# RC_Engine_Sound_ESP32.net
KiCad netlist of a schematic drawn in EAGLE
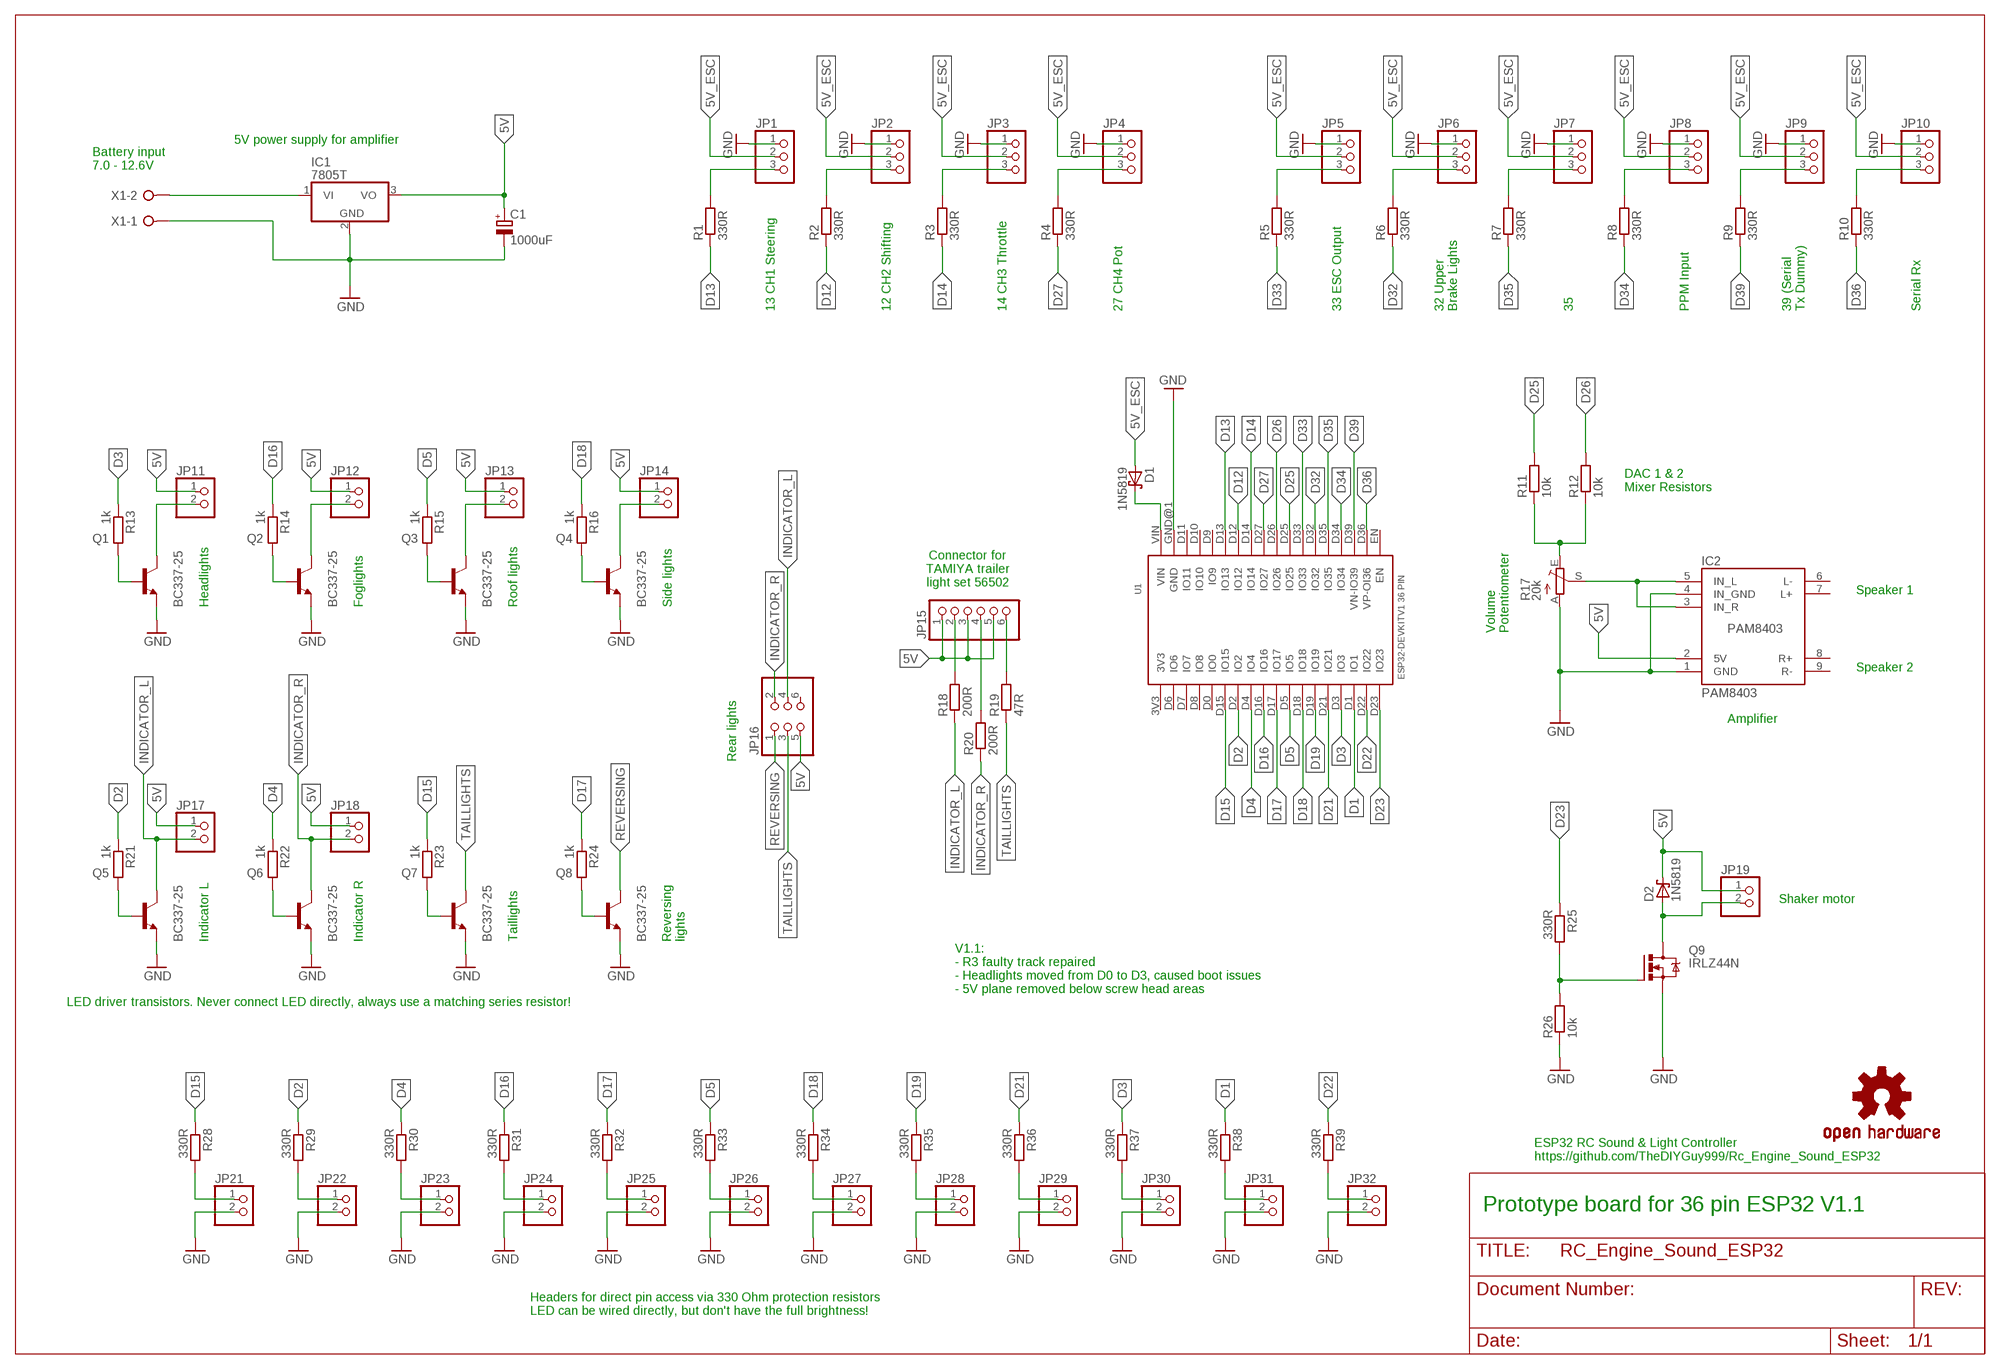
[diagram p0: schematic, sheet 1]

(export (version "E")
  (design (tool "Eeschema 10.0.6"))
  (components
    (comp (ref "C1")
      (value "1000uF")
      (footprint "eagle-import:E5-10,5")
      (libsource (lib "eagle-import") (part "CPOL-EUE5-10.5"))
    )
    (comp (ref "D1")
      (value "1N5819")
      (footprint "eagle-import:DO35-7")
      (libsource (lib "eagle-import") (part "SCHOTTKY-DIODEDO35-7"))
    )
    (comp (ref "D2")
      (value "1N5819")
      (footprint "eagle-import:DO35-7")
      (libsource (lib "eagle-import") (part "SCHOTTKY-DIODEDO35-7"))
    )
    (comp (ref "IC1")
      (value "7805T")
      (footprint "eagle-import:TO220H")
      (libsource (lib "eagle-import") (part "78T05"))
    )
    (comp (ref "IC2")
      (value "PAM8403")
      (footprint "eagle-import:PAM8403")
      (libsource (lib "eagle-import") (part "PAM8403"))
    )
    (comp (ref "JP1")
      (value "PINHD-1X3")
      (footprint "eagle-import:1X03")
      (libsource (lib "eagle-import") (part "PINHD-1X3"))
    )
    (comp (ref "JP2")
      (value "PINHD-1X3")
      (footprint "eagle-import:1X03")
      (libsource (lib "eagle-import") (part "PINHD-1X3"))
    )
    (comp (ref "JP3")
      (value "PINHD-1X3")
      (footprint "eagle-import:1X03")
      (libsource (lib "eagle-import") (part "PINHD-1X3"))
    )
    (comp (ref "JP4")
      (value "PINHD-1X3")
      (footprint "eagle-import:1X03")
      (libsource (lib "eagle-import") (part "PINHD-1X3"))
    )
    (comp (ref "JP5")
      (value "PINHD-1X3")
      (footprint "eagle-import:1X03")
      (libsource (lib "eagle-import") (part "PINHD-1X3"))
    )
    (comp (ref "JP6")
      (value "PINHD-1X3")
      (footprint "eagle-import:1X03")
      (libsource (lib "eagle-import") (part "PINHD-1X3"))
    )
    (comp (ref "JP7")
      (value "PINHD-1X3")
      (footprint "eagle-import:1X03")
      (libsource (lib "eagle-import") (part "PINHD-1X3"))
    )
    (comp (ref "JP8")
      (value "PINHD-1X3")
      (footprint "eagle-import:1X03")
      (libsource (lib "eagle-import") (part "PINHD-1X3"))
    )
    (comp (ref "JP9")
      (value "PINHD-1X3")
      (footprint "eagle-import:1X03")
      (libsource (lib "eagle-import") (part "PINHD-1X3"))
    )
    (comp (ref "JP10")
      (value "PINHD-1X3")
      (footprint "eagle-import:1X03")
      (libsource (lib "eagle-import") (part "PINHD-1X3"))
    )
    (comp (ref "JP11")
      (value "PINHD-1X2")
      (footprint "eagle-import:1X02")
      (libsource (lib "eagle-import") (part "PINHD-1X2"))
    )
    (comp (ref "JP12")
      (value "PINHD-1X2")
      (footprint "eagle-import:1X02")
      (libsource (lib "eagle-import") (part "PINHD-1X2"))
    )
    (comp (ref "JP13")
      (value "PINHD-1X2")
      (footprint "eagle-import:1X02")
      (libsource (lib "eagle-import") (part "PINHD-1X2"))
    )
    (comp (ref "JP14")
      (value "PINHD-1X2")
      (footprint "eagle-import:1X02")
      (libsource (lib "eagle-import") (part "PINHD-1X2"))
    )
    (comp (ref "JP15")
      (value "PINHD-1X6")
      (footprint "eagle-import:1X06")
      (libsource (lib "eagle-import") (part "PINHD-1X6"))
    )
    (comp (ref "JP16")
      (value "PINHD-2X3")
      (footprint "eagle-import:2X03")
      (libsource (lib "eagle-import") (part "PINHD-2X3"))
    )
    (comp (ref "JP17")
      (value "PINHD-1X2")
      (footprint "eagle-import:1X02")
      (libsource (lib "eagle-import") (part "PINHD-1X2"))
    )
    (comp (ref "JP18")
      (value "PINHD-1X2")
      (footprint "eagle-import:1X02")
      (libsource (lib "eagle-import") (part "PINHD-1X2"))
    )
    (comp (ref "JP19")
      (value "PINHD-1X2")
      (footprint "eagle-import:1X02")
      (libsource (lib "eagle-import") (part "PINHD-1X2"))
    )
    (comp (ref "JP21")
      (value "PINHD-1X2")
      (footprint "eagle-import:1X02")
      (libsource (lib "eagle-import") (part "PINHD-1X2"))
    )
    (comp (ref "JP22")
      (value "PINHD-1X2")
      (footprint "eagle-import:1X02")
      (libsource (lib "eagle-import") (part "PINHD-1X2"))
    )
    (comp (ref "JP23")
      (value "PINHD-1X2")
      (footprint "eagle-import:1X02")
      (libsource (lib "eagle-import") (part "PINHD-1X2"))
    )
    (comp (ref "JP24")
      (value "PINHD-1X2")
      (footprint "eagle-import:1X02")
      (libsource (lib "eagle-import") (part "PINHD-1X2"))
    )
    (comp (ref "JP25")
      (value "PINHD-1X2")
      (footprint "eagle-import:1X02")
      (libsource (lib "eagle-import") (part "PINHD-1X2"))
    )
    (comp (ref "JP26")
      (value "PINHD-1X2")
      (footprint "eagle-import:1X02")
      (libsource (lib "eagle-import") (part "PINHD-1X2"))
    )
    (comp (ref "JP27")
      (value "PINHD-1X2")
      (footprint "eagle-import:1X02")
      (libsource (lib "eagle-import") (part "PINHD-1X2"))
    )
    (comp (ref "JP28")
      (value "PINHD-1X2")
      (footprint "eagle-import:1X02")
      (libsource (lib "eagle-import") (part "PINHD-1X2"))
    )
    (comp (ref "JP29")
      (value "PINHD-1X2")
      (footprint "eagle-import:1X02")
      (libsource (lib "eagle-import") (part "PINHD-1X2"))
    )
    (comp (ref "JP30")
      (value "PINHD-1X2")
      (footprint "eagle-import:1X02")
      (libsource (lib "eagle-import") (part "PINHD-1X2"))
    )
    (comp (ref "JP31")
      (value "PINHD-1X2")
      (footprint "eagle-import:1X02")
      (libsource (lib "eagle-import") (part "PINHD-1X2"))
    )
    (comp (ref "JP32")
      (value "PINHD-1X2")
      (footprint "eagle-import:1X02")
      (libsource (lib "eagle-import") (part "PINHD-1X2"))
    )
    (comp (ref "LOGO1")
      (value "OSHW-LOGOM")
      (footprint "eagle-import:OSHW-LOGO-M")
      (libsource (lib "eagle-import") (part "OSHW-LOGOM"))
    )
    (comp (ref "Q1")
      (value "BC337-25")
      (footprint "eagle-import:TO92")
      (libsource (lib "eagle-import") (part "BC337-25"))
    )
    (comp (ref "Q2")
      (value "BC337-25")
      (footprint "eagle-import:TO92")
      (libsource (lib "eagle-import") (part "BC337-25"))
    )
    (comp (ref "Q3")
      (value "BC337-25")
      (footprint "eagle-import:TO92")
      (libsource (lib "eagle-import") (part "BC337-25"))
    )
    (comp (ref "Q4")
      (value "BC337-25")
      (footprint "eagle-import:TO92")
      (libsource (lib "eagle-import") (part "BC337-25"))
    )
    (comp (ref "Q5")
      (value "BC337-25")
      (footprint "eagle-import:TO92")
      (libsource (lib "eagle-import") (part "BC337-25"))
    )
    (comp (ref "Q6")
      (value "BC337-25")
      (footprint "eagle-import:TO92")
      (libsource (lib "eagle-import") (part "BC337-25"))
    )
    (comp (ref "Q7")
      (value "BC337-25")
      (footprint "eagle-import:TO92")
      (libsource (lib "eagle-import") (part "BC337-25"))
    )
    (comp (ref "Q8")
      (value "BC337-25")
      (footprint "eagle-import:TO92")
      (libsource (lib "eagle-import") (part "BC337-25"))
    )
    (comp (ref "Q9")
      (value "IRLZ44N")
      (footprint "eagle-import:TO220BV")
      (libsource (lib "eagle-import") (part "IRF540"))
    )
    (comp (ref "R1")
      (value "330R")
      (footprint "eagle-import:0207_2V")
      (libsource (lib "eagle-import") (part "R-EU_0207/2V"))
    )
    (comp (ref "R2")
      (value "330R")
      (footprint "eagle-import:0207_2V")
      (libsource (lib "eagle-import") (part "R-EU_0207/2V"))
    )
    (comp (ref "R3")
      (value "330R")
      (footprint "eagle-import:0207_2V")
      (libsource (lib "eagle-import") (part "R-EU_0207/2V"))
    )
    (comp (ref "R4")
      (value "330R")
      (footprint "eagle-import:0207_2V")
      (libsource (lib "eagle-import") (part "R-EU_0207/2V"))
    )
    (comp (ref "R5")
      (value "330R")
      (footprint "eagle-import:0207_2V")
      (libsource (lib "eagle-import") (part "R-EU_0207/2V"))
    )
    (comp (ref "R6")
      (value "330R")
      (footprint "eagle-import:0207_2V")
      (libsource (lib "eagle-import") (part "R-EU_0207/2V"))
    )
    (comp (ref "R7")
      (value "330R")
      (footprint "eagle-import:0207_2V")
      (libsource (lib "eagle-import") (part "R-EU_0207/2V"))
    )
    (comp (ref "R8")
      (value "330R")
      (footprint "eagle-import:0207_2V")
      (libsource (lib "eagle-import") (part "R-EU_0207/2V"))
    )
    (comp (ref "R9")
      (value "330R")
      (footprint "eagle-import:0207_2V")
      (libsource (lib "eagle-import") (part "R-EU_0207/2V"))
    )
    (comp (ref "R10")
      (value "330R")
      (footprint "eagle-import:0207_2V")
      (libsource (lib "eagle-import") (part "R-EU_0207/2V"))
    )
    (comp (ref "R11")
      (value "10k")
      (footprint "eagle-import:0207_10")
      (libsource (lib "eagle-import") (part "R-EU_0207/10"))
    )
    (comp (ref "R12")
      (value "10k")
      (footprint "eagle-import:0207_10")
      (libsource (lib "eagle-import") (part "R-EU_0207/10"))
    )
    (comp (ref "R13")
      (value "1k")
      (footprint "eagle-import:0207_2V")
      (libsource (lib "eagle-import") (part "R-EU_0207/2V"))
    )
    (comp (ref "R14")
      (value "1k")
      (footprint "eagle-import:0207_2V")
      (libsource (lib "eagle-import") (part "R-EU_0207/2V"))
    )
    (comp (ref "R15")
      (value "1k")
      (footprint "eagle-import:0207_2V")
      (libsource (lib "eagle-import") (part "R-EU_0207/2V"))
    )
    (comp (ref "R16")
      (value "1k")
      (footprint "eagle-import:0207_2V")
      (libsource (lib "eagle-import") (part "R-EU_0207/2V"))
    )
    (comp (ref "R17")
      (value "20k")
      (footprint "eagle-import:S64W")
      (libsource (lib "eagle-import") (part "TRIM_EU-S64W"))
    )
    (comp (ref "R18")
      (value "200R")
      (footprint "eagle-import:0207_2V")
      (libsource (lib "eagle-import") (part "R-EU_0207/2V"))
    )
    (comp (ref "R19")
      (value "47R")
      (footprint "eagle-import:0207_2V")
      (libsource (lib "eagle-import") (part "R-EU_0207/2V"))
    )
    (comp (ref "R20")
      (value "200R")
      (footprint "eagle-import:0207_2V")
      (libsource (lib "eagle-import") (part "R-EU_0207/2V"))
    )
    (comp (ref "R21")
      (value "1k")
      (footprint "eagle-import:0207_2V")
      (libsource (lib "eagle-import") (part "R-EU_0207/2V"))
    )
    (comp (ref "R22")
      (value "1k")
      (footprint "eagle-import:0207_2V")
      (libsource (lib "eagle-import") (part "R-EU_0207/2V"))
    )
    (comp (ref "R23")
      (value "1k")
      (footprint "eagle-import:0207_2V")
      (libsource (lib "eagle-import") (part "R-EU_0207/2V"))
    )
    (comp (ref "R24")
      (value "1k")
      (footprint "eagle-import:0207_2V")
      (libsource (lib "eagle-import") (part "R-EU_0207/2V"))
    )
    (comp (ref "R25")
      (value "330R")
      (footprint "eagle-import:0207_2V")
      (libsource (lib "eagle-import") (part "R-EU_0207/2V"))
    )
    (comp (ref "R26")
      (value "10k")
      (footprint "eagle-import:0207_2V")
      (libsource (lib "eagle-import") (part "R-EU_0207/2V"))
    )
    (comp (ref "R28")
      (value "330R")
      (footprint "eagle-import:0207_2V")
      (libsource (lib "eagle-import") (part "R-EU_0207/2V"))
    )
    (comp (ref "R29")
      (value "330R")
      (footprint "eagle-import:0207_2V")
      (libsource (lib "eagle-import") (part "R-EU_0207/2V"))
    )
    (comp (ref "R30")
      (value "330R")
      (footprint "eagle-import:0207_2V")
      (libsource (lib "eagle-import") (part "R-EU_0207/2V"))
    )
    (comp (ref "R31")
      (value "330R")
      (footprint "eagle-import:0207_2V")
      (libsource (lib "eagle-import") (part "R-EU_0207/2V"))
    )
    (comp (ref "R32")
      (value "330R")
      (footprint "eagle-import:0207_2V")
      (libsource (lib "eagle-import") (part "R-EU_0207/2V"))
    )
    (comp (ref "R33")
      (value "330R")
      (footprint "eagle-import:0207_2V")
      (libsource (lib "eagle-import") (part "R-EU_0207/2V"))
    )
    (comp (ref "R34")
      (value "330R")
      (footprint "eagle-import:0207_2V")
      (libsource (lib "eagle-import") (part "R-EU_0207/2V"))
    )
    (comp (ref "R35")
      (value "330R")
      (footprint "eagle-import:0207_2V")
      (libsource (lib "eagle-import") (part "R-EU_0207/2V"))
    )
    (comp (ref "R36")
      (value "330R")
      (footprint "eagle-import:0207_2V")
      (libsource (lib "eagle-import") (part "R-EU_0207/2V"))
    )
    (comp (ref "R37")
      (value "330R")
      (footprint "eagle-import:0207_2V")
      (libsource (lib "eagle-import") (part "R-EU_0207/2V"))
    )
    (comp (ref "R38")
      (value "330R")
      (footprint "eagle-import:0207_2V")
      (libsource (lib "eagle-import") (part "R-EU_0207/2V"))
    )
    (comp (ref "R39")
      (value "330R")
      (footprint "eagle-import:0207_2V")
      (libsource (lib "eagle-import") (part "R-EU_0207/2V"))
    )
    (comp (ref "U1")
      (value "ESP32DEVKITV1")
      (footprint "eagle-import:ESP32-DEVKITV1")
      (libsource (lib "eagle-import") (part "ESP32DEVKITV1"))
    )
    (comp (ref "X1")
      (value "W237-02P")
      (footprint "eagle-import:W237-132")
      (libsource (lib "eagle-import") (part "W237-02P"))
    )
  )
  (nets
    (net (code "1") (name "5V") (class "Default")
      (node (ref "C1") (pin "+") (pinfunction "+_+") (pintype "passive"))
      (node (ref "D2") (pin "C") (pinfunction "C_C") (pintype "passive"))
      (node (ref "IC1") (pin "3") (pinfunction "VO_3") (pintype "passive"))
      (node (ref "IC2") (pin "2") (pinfunction "5V_2") (pintype "input"))
      (node (ref "JP11") (pin "1") (pinfunction "1_1") (pintype "passive"))
      (node (ref "JP12") (pin "1") (pinfunction "1_1") (pintype "passive"))
      (node (ref "JP13") (pin "1") (pinfunction "1_1") (pintype "passive"))
      (node (ref "JP14") (pin "1") (pinfunction "1_1") (pintype "passive"))
      (node (ref "JP15") (pin "1") (pinfunction "1_1") (pintype "passive"))
      (node (ref "JP15") (pin "3") (pinfunction "3_3") (pintype "passive"))
      (node (ref "JP15") (pin "5") (pinfunction "5_5") (pintype "passive"))
      (node (ref "JP16") (pin "5") (pinfunction "5_5") (pintype "passive"))
      (node (ref "JP17") (pin "1") (pinfunction "1_1") (pintype "passive"))
      (node (ref "JP18") (pin "1") (pinfunction "1_1") (pintype "passive"))
      (node (ref "JP19") (pin "1") (pinfunction "1_1") (pintype "passive"))
    )
    (net (code "2") (name "5V_ESC") (class "Default")
      (node (ref "D1") (pin "A") (pinfunction "A_A") (pintype "passive"))
      (node (ref "JP1") (pin "2") (pinfunction "2_2") (pintype "passive"))
      (node (ref "JP10") (pin "2") (pinfunction "2_2") (pintype "passive"))
      (node (ref "JP2") (pin "2") (pinfunction "2_2") (pintype "passive"))
      (node (ref "JP3") (pin "2") (pinfunction "2_2") (pintype "passive"))
      (node (ref "JP4") (pin "2") (pinfunction "2_2") (pintype "passive"))
      (node (ref "JP5") (pin "2") (pinfunction "2_2") (pintype "passive"))
      (node (ref "JP6") (pin "2") (pinfunction "2_2") (pintype "passive"))
      (node (ref "JP7") (pin "2") (pinfunction "2_2") (pintype "passive"))
      (node (ref "JP8") (pin "2") (pinfunction "2_2") (pintype "passive"))
      (node (ref "JP9") (pin "2") (pinfunction "2_2") (pintype "passive"))
    )
    (net (code "3") (name "D1") (class "Default")
      (node (ref "R38") (pin "1") (pinfunction "1_1") (pintype "passive"))
      (node (ref "U1") (pin "D1") (pinfunction "IO1_D1") (pintype "bidirectional"))
    )
    (net (code "4") (name "D2") (class "Default")
      (node (ref "R21") (pin "1") (pinfunction "1_1") (pintype "passive"))
      (node (ref "R29") (pin "1") (pinfunction "1_1") (pintype "passive"))
      (node (ref "U1") (pin "D2") (pinfunction "IO2_D2") (pintype "bidirectional"))
    )
    (net (code "5") (name "D3") (class "Default")
      (node (ref "R13") (pin "1") (pinfunction "1_1") (pintype "passive"))
      (node (ref "R37") (pin "1") (pinfunction "1_1") (pintype "passive"))
      (node (ref "U1") (pin "D3") (pinfunction "IO3_D3") (pintype "bidirectional"))
    )
    (net (code "6") (name "D4") (class "Default")
      (node (ref "R22") (pin "1") (pinfunction "1_1") (pintype "passive"))
      (node (ref "R30") (pin "1") (pinfunction "1_1") (pintype "passive"))
      (node (ref "U1") (pin "D4") (pinfunction "IO4_D4") (pintype "bidirectional"))
    )
    (net (code "7") (name "D5") (class "Default")
      (node (ref "R15") (pin "1") (pinfunction "1_1") (pintype "passive"))
      (node (ref "R33") (pin "1") (pinfunction "1_1") (pintype "passive"))
      (node (ref "U1") (pin "D5") (pinfunction "IO5_D5") (pintype "bidirectional"))
    )
    (net (code "8") (name "D12") (class "Default")
      (node (ref "R2") (pin "1") (pinfunction "1_1") (pintype "passive"))
      (node (ref "U1") (pin "D12") (pinfunction "IO12_D12") (pintype "bidirectional"))
    )
    (net (code "9") (name "D13") (class "Default")
      (node (ref "R1") (pin "1") (pinfunction "1_1") (pintype "passive"))
      (node (ref "U1") (pin "D13") (pinfunction "IO13_D13") (pintype "bidirectional"))
    )
    (net (code "10") (name "D14") (class "Default")
      (node (ref "R3") (pin "1") (pinfunction "1_1") (pintype "passive"))
      (node (ref "U1") (pin "D14") (pinfunction "IO14_D14") (pintype "bidirectional"))
    )
    (net (code "11") (name "D15") (class "Default")
      (node (ref "R23") (pin "1") (pinfunction "1_1") (pintype "passive"))
      (node (ref "R28") (pin "1") (pinfunction "1_1") (pintype "passive"))
      (node (ref "U1") (pin "D15") (pinfunction "IO15_D15") (pintype "bidirectional"))
    )
    (net (code "12") (name "D16") (class "Default")
      (node (ref "R14") (pin "1") (pinfunction "1_1") (pintype "passive"))
      (node (ref "R31") (pin "1") (pinfunction "1_1") (pintype "passive"))
      (node (ref "U1") (pin "D16") (pinfunction "IO16_D16") (pintype "bidirectional"))
    )
    (net (code "13") (name "D17") (class "Default")
      (node (ref "R24") (pin "1") (pinfunction "1_1") (pintype "passive"))
      (node (ref "R32") (pin "1") (pinfunction "1_1") (pintype "passive"))
      (node (ref "U1") (pin "D17") (pinfunction "IO17_D17") (pintype "bidirectional"))
    )
    (net (code "14") (name "D18") (class "Default")
      (node (ref "R16") (pin "1") (pinfunction "1_1") (pintype "passive"))
      (node (ref "R34") (pin "1") (pinfunction "1_1") (pintype "passive"))
      (node (ref "U1") (pin "D18") (pinfunction "IO18_D18") (pintype "bidirectional"))
    )
    (net (code "15") (name "D19") (class "Default")
      (node (ref "R35") (pin "1") (pinfunction "1_1") (pintype "passive"))
      (node (ref "U1") (pin "D19") (pinfunction "IO19_D19") (pintype "bidirectional"))
    )
    (net (code "16") (name "D21") (class "Default")
      (node (ref "R36") (pin "1") (pinfunction "1_1") (pintype "passive"))
      (node (ref "U1") (pin "D21") (pinfunction "IO21_D21") (pintype "bidirectional"))
    )
    (net (code "17") (name "D22") (class "Default")
      (node (ref "R39") (pin "1") (pinfunction "1_1") (pintype "passive"))
      (node (ref "U1") (pin "D22") (pinfunction "IO22_D22") (pintype "bidirectional"))
    )
    (net (code "18") (name "D23") (class "Default")
      (node (ref "R25") (pin "1") (pinfunction "1_1") (pintype "passive"))
      (node (ref "U1") (pin "D23") (pinfunction "IO23_D23") (pintype "bidirectional"))
    )
    (net (code "19") (name "D25") (class "Default")
      (node (ref "R11") (pin "2") (pinfunction "2_2") (pintype "passive"))
      (node (ref "U1") (pin "D25") (pinfunction "IO25_D25") (pintype "bidirectional"))
    )
    (net (code "20") (name "D26") (class "Default")
      (node (ref "R12") (pin "2") (pinfunction "2_2") (pintype "passive"))
      (node (ref "U1") (pin "D26") (pinfunction "IO26_D26") (pintype "bidirectional"))
    )
    (net (code "21") (name "D27") (class "Default")
      (node (ref "R4") (pin "1") (pinfunction "1_1") (pintype "passive"))
      (node (ref "U1") (pin "D27") (pinfunction "IO27_D27") (pintype "bidirectional"))
    )
    (net (code "22") (name "D32") (class "Default")
      (node (ref "R6") (pin "1") (pinfunction "1_1") (pintype "passive"))
      (node (ref "U1") (pin "D32") (pinfunction "IO32_D32") (pintype "bidirectional"))
    )
    (net (code "23") (name "D33") (class "Default")
      (node (ref "R5") (pin "1") (pinfunction "1_1") (pintype "passive"))
      (node (ref "U1") (pin "D33") (pinfunction "IO33_D33") (pintype "bidirectional"))
    )
    (net (code "24") (name "D34") (class "Default")
      (node (ref "R8") (pin "1") (pinfunction "1_1") (pintype "passive"))
      (node (ref "U1") (pin "D34") (pinfunction "IO34_D34") (pintype "bidirectional"))
    )
    (net (code "25") (name "D35") (class "Default")
      (node (ref "R7") (pin "1") (pinfunction "1_1") (pintype "passive"))
      (node (ref "U1") (pin "D35") (pinfunction "IO35_D35") (pintype "bidirectional"))
    )
    (net (code "26") (name "D36") (class "Default")
      (node (ref "R10") (pin "1") (pinfunction "1_1") (pintype "passive"))
      (node (ref "U1") (pin "D36") (pinfunction "VP-OI36_D36") (pintype "bidirectional"))
    )
    (net (code "27") (name "D39") (class "Default")
      (node (ref "R9") (pin "1") (pinfunction "1_1") (pintype "passive"))
      (node (ref "U1") (pin "D39") (pinfunction "VN-IO39_D39") (pintype "bidirectional"))
    )
    (net (code "28") (name "GND") (class "Default")
      (node (ref "C1") (pin "-") (pinfunction "-_-") (pintype "passive"))
      (node (ref "IC1") (pin "2") (pinfunction "GND_2") (pintype "passive"))
      (node (ref "IC2") (pin "1") (pinfunction "GND_1") (pintype "input"))
      (node (ref "IC2") (pin "4") (pinfunction "IN_GND_4") (pintype "input"))
      (node (ref "JP1") (pin "1") (pinfunction "1_1") (pintype "passive"))
      (node (ref "JP10") (pin "1") (pinfunction "1_1") (pintype "passive"))
      (node (ref "JP2") (pin "1") (pinfunction "1_1") (pintype "passive"))
      (node (ref "JP21") (pin "2") (pinfunction "2_2") (pintype "passive"))
      (node (ref "JP22") (pin "2") (pinfunction "2_2") (pintype "passive"))
      (node (ref "JP23") (pin "2") (pinfunction "2_2") (pintype "passive"))
      (node (ref "JP24") (pin "2") (pinfunction "2_2") (pintype "passive"))
      (node (ref "JP25") (pin "2") (pinfunction "2_2") (pintype "passive"))
      (node (ref "JP26") (pin "2") (pinfunction "2_2") (pintype "passive"))
      (node (ref "JP27") (pin "2") (pinfunction "2_2") (pintype "passive"))
      (node (ref "JP28") (pin "2") (pinfunction "2_2") (pintype "passive"))
      (node (ref "JP29") (pin "2") (pinfunction "2_2") (pintype "passive"))
      (node (ref "JP3") (pin "1") (pinfunction "1_1") (pintype "passive"))
      (node (ref "JP30") (pin "2") (pinfunction "2_2") (pintype "passive"))
      (node (ref "JP31") (pin "2") (pinfunction "2_2") (pintype "passive"))
      (node (ref "JP32") (pin "2") (pinfunction "2_2") (pintype "passive"))
      (node (ref "JP4") (pin "1") (pinfunction "1_1") (pintype "passive"))
      (node (ref "JP5") (pin "1") (pinfunction "1_1") (pintype "passive"))
      (node (ref "JP6") (pin "1") (pinfunction "1_1") (pintype "passive"))
      (node (ref "JP7") (pin "1") (pinfunction "1_1") (pintype "passive"))
      (node (ref "JP8") (pin "1") (pinfunction "1_1") (pintype "passive"))
      (node (ref "JP9") (pin "1") (pinfunction "1_1") (pintype "passive"))
      (node (ref "Q1") (pin "1") (pinfunction "E_1") (pintype "passive"))
      (node (ref "Q2") (pin "1") (pinfunction "E_1") (pintype "passive"))
      (node (ref "Q3") (pin "1") (pinfunction "E_1") (pintype "passive"))
      (node (ref "Q4") (pin "1") (pinfunction "E_1") (pintype "passive"))
      (node (ref "Q5") (pin "1") (pinfunction "E_1") (pintype "passive"))
      (node (ref "Q6") (pin "1") (pinfunction "E_1") (pintype "passive"))
      (node (ref "Q7") (pin "1") (pinfunction "E_1") (pintype "passive"))
      (node (ref "Q8") (pin "1") (pinfunction "E_1") (pintype "passive"))
      (node (ref "Q9") (pin "S") (pinfunction "S_S") (pintype "passive"))
      (node (ref "R17") (pin "A") (pinfunction "A_A") (pintype "passive"))
      (node (ref "R26") (pin "1") (pinfunction "1_1") (pintype "passive"))
      (node (ref "U1") (pin "GND@1") (pinfunction "GND_GND@1") (pintype "bidirectional"))
      (node (ref "X1") (pin "1") (pinfunction "KL_1") (pintype "passive"))
    )
    (net (code "29") (name "INDICATOR_L") (class "Default")
      (node (ref "JP16") (pin "4") (pinfunction "4_4") (pintype "passive"))
      (node (ref "JP17") (pin "2") (pinfunction "2_2") (pintype "passive"))
      (node (ref "Q5") (pin "3") (pinfunction "C_3") (pintype "passive"))
      (node (ref "R18") (pin "1") (pinfunction "1_1") (pintype "passive"))
    )
    (net (code "30") (name "INDICATOR_R") (class "Default")
      (node (ref "JP16") (pin "2") (pinfunction "2_2") (pintype "passive"))
      (node (ref "JP18") (pin "2") (pinfunction "2_2") (pintype "passive"))
      (node (ref "Q6") (pin "3") (pinfunction "C_3") (pintype "passive"))
      (node (ref "R20") (pin "1") (pinfunction "1_1") (pintype "passive"))
    )
    (net (code "31") (name "Net-(D1-PadC)") (class "Default")
      (node (ref "D1") (pin "C") (pinfunction "C_C") (pintype "passive"))
      (node (ref "U1") (pin "VIN") (pinfunction "VIN_VIN") (pintype "bidirectional"))
    )
    (net (code "32") (name "Net-(D2-PadA)") (class "Default")
      (node (ref "D2") (pin "A") (pinfunction "A_A") (pintype "passive"))
      (node (ref "JP19") (pin "2") (pinfunction "2_2") (pintype "passive"))
      (node (ref "Q9") (pin "D") (pinfunction "D_D") (pintype "passive"))
    )
    (net (code "33") (name "Net-(IC1-VI)") (class "Default")
      (node (ref "IC1") (pin "1") (pinfunction "VI_1") (pintype "input"))
      (node (ref "X1") (pin "2") (pinfunction "KL_2") (pintype "passive"))
    )
    (net (code "34") (name "Net-(IC2-IN_L)") (class "Default")
      (node (ref "IC2") (pin "3") (pinfunction "IN_R_3") (pintype "input"))
      (node (ref "IC2") (pin "5") (pinfunction "IN_L_5") (pintype "input"))
      (node (ref "R17") (pin "S") (pinfunction "S_S") (pintype "passive"))
    )
    (net (code "35") (name "Net-(JP1-Pad3)") (class "Default")
      (node (ref "JP1") (pin "3") (pinfunction "3_3") (pintype "passive"))
      (node (ref "R1") (pin "2") (pinfunction "2_2") (pintype "passive"))
    )
    (net (code "36") (name "Net-(JP2-Pad3)") (class "Default")
      (node (ref "JP2") (pin "3") (pinfunction "3_3") (pintype "passive"))
      (node (ref "R2") (pin "2") (pinfunction "2_2") (pintype "passive"))
    )
    (net (code "37") (name "Net-(JP3-Pad3)") (class "Default")
      (node (ref "JP3") (pin "3") (pinfunction "3_3") (pintype "passive"))
      (node (ref "R3") (pin "2") (pinfunction "2_2") (pintype "passive"))
    )
    (net (code "38") (name "Net-(JP4-Pad3)") (class "Default")
      (node (ref "JP4") (pin "3") (pinfunction "3_3") (pintype "passive"))
      (node (ref "R4") (pin "2") (pinfunction "2_2") (pintype "passive"))
    )
    (net (code "39") (name "Net-(JP5-Pad3)") (class "Default")
      (node (ref "JP5") (pin "3") (pinfunction "3_3") (pintype "passive"))
      (node (ref "R5") (pin "2") (pinfunction "2_2") (pintype "passive"))
    )
    (net (code "40") (name "Net-(JP6-Pad3)") (class "Default")
      (node (ref "JP6") (pin "3") (pinfunction "3_3") (pintype "passive"))
      (node (ref "R6") (pin "2") (pinfunction "2_2") (pintype "passive"))
    )
    (net (code "41") (name "Net-(JP7-Pad3)") (class "Default")
      (node (ref "JP7") (pin "3") (pinfunction "3_3") (pintype "passive"))
      (node (ref "R7") (pin "2") (pinfunction "2_2") (pintype "passive"))
    )
    (net (code "42") (name "Net-(JP8-Pad3)") (class "Default")
      (node (ref "JP8") (pin "3") (pinfunction "3_3") (pintype "passive"))
      (node (ref "R8") (pin "2") (pinfunction "2_2") (pintype "passive"))
    )
    (net (code "43") (name "Net-(JP9-Pad3)") (class "Default")
      (node (ref "JP9") (pin "3") (pinfunction "3_3") (pintype "passive"))
      (node (ref "R9") (pin "2") (pinfunction "2_2") (pintype "passive"))
    )
    (net (code "44") (name "Net-(JP10-Pad3)") (class "Default")
      (node (ref "JP10") (pin "3") (pinfunction "3_3") (pintype "passive"))
      (node (ref "R10") (pin "2") (pinfunction "2_2") (pintype "passive"))
    )
    (net (code "45") (name "Net-(JP15-Pad2)") (class "Default")
      (node (ref "JP15") (pin "2") (pinfunction "2_2") (pintype "passive"))
      (node (ref "R18") (pin "2") (pinfunction "2_2") (pintype "passive"))
    )
    (net (code "46") (name "Net-(JP15-Pad4)") (class "Default")
      (node (ref "JP15") (pin "4") (pinfunction "4_4") (pintype "passive"))
      (node (ref "R20") (pin "2") (pinfunction "2_2") (pintype "passive"))
    )
    (net (code "47") (name "Net-(JP15-Pad6)") (class "Default")
      (node (ref "JP15") (pin "6") (pinfunction "6_6") (pintype "passive"))
      (node (ref "R19") (pin "2") (pinfunction "2_2") (pintype "passive"))
    )
    (net (code "48") (name "Net-(JP21-Pad1)") (class "Default")
      (node (ref "JP21") (pin "1") (pinfunction "1_1") (pintype "passive"))
      (node (ref "R28") (pin "2") (pinfunction "2_2") (pintype "passive"))
    )
    (net (code "49") (name "Net-(JP22-Pad1)") (class "Default")
      (node (ref "JP22") (pin "1") (pinfunction "1_1") (pintype "passive"))
      (node (ref "R29") (pin "2") (pinfunction "2_2") (pintype "passive"))
    )
    (net (code "50") (name "Net-(JP23-Pad1)") (class "Default")
      (node (ref "JP23") (pin "1") (pinfunction "1_1") (pintype "passive"))
      (node (ref "R30") (pin "2") (pinfunction "2_2") (pintype "passive"))
    )
    (net (code "51") (name "Net-(JP24-Pad1)") (class "Default")
      (node (ref "JP24") (pin "1") (pinfunction "1_1") (pintype "passive"))
      (node (ref "R31") (pin "2") (pinfunction "2_2") (pintype "passive"))
    )
    (net (code "52") (name "Net-(JP25-Pad1)") (class "Default")
      (node (ref "JP25") (pin "1") (pinfunction "1_1") (pintype "passive"))
      (node (ref "R32") (pin "2") (pinfunction "2_2") (pintype "passive"))
    )
    (net (code "53") (name "Net-(JP26-Pad1)") (class "Default")
      (node (ref "JP26") (pin "1") (pinfunction "1_1") (pintype "passive"))
      (node (ref "R33") (pin "2") (pinfunction "2_2") (pintype "passive"))
    )
    (net (code "54") (name "Net-(JP27-Pad1)") (class "Default")
      (node (ref "JP27") (pin "1") (pinfunction "1_1") (pintype "passive"))
      (node (ref "R34") (pin "2") (pinfunction "2_2") (pintype "passive"))
    )
    (net (code "55") (name "Net-(JP28-Pad1)") (class "Default")
      (node (ref "JP28") (pin "1") (pinfunction "1_1") (pintype "passive"))
      (node (ref "R35") (pin "2") (pinfunction "2_2") (pintype "passive"))
    )
    (net (code "56") (name "Net-(JP29-Pad1)") (class "Default")
      (node (ref "JP29") (pin "1") (pinfunction "1_1") (pintype "passive"))
      (node (ref "R36") (pin "2") (pinfunction "2_2") (pintype "passive"))
    )
    (net (code "57") (name "Net-(JP30-Pad1)") (class "Default")
      (node (ref "JP30") (pin "1") (pinfunction "1_1") (pintype "passive"))
      (node (ref "R37") (pin "2") (pinfunction "2_2") (pintype "passive"))
    )
    (net (code "58") (name "Net-(JP31-Pad1)") (class "Default")
      (node (ref "JP31") (pin "1") (pinfunction "1_1") (pintype "passive"))
      (node (ref "R38") (pin "2") (pinfunction "2_2") (pintype "passive"))
    )
    (net (code "59") (name "Net-(JP32-Pad1)") (class "Default")
      (node (ref "JP32") (pin "1") (pinfunction "1_1") (pintype "passive"))
      (node (ref "R39") (pin "2") (pinfunction "2_2") (pintype "passive"))
    )
    (net (code "60") (name "Net-(Q1-B)") (class "Default")
      (node (ref "Q1") (pin "2") (pinfunction "B_2") (pintype "passive"))
      (node (ref "R13") (pin "2") (pinfunction "2_2") (pintype "passive"))
    )
    (net (code "61") (name "Net-(Q1-C)") (class "Default")
      (node (ref "JP11") (pin "2") (pinfunction "2_2") (pintype "passive"))
      (node (ref "Q1") (pin "3") (pinfunction "C_3") (pintype "passive"))
    )
    (net (code "62") (name "Net-(Q2-B)") (class "Default")
      (node (ref "Q2") (pin "2") (pinfunction "B_2") (pintype "passive"))
      (node (ref "R14") (pin "2") (pinfunction "2_2") (pintype "passive"))
    )
    (net (code "63") (name "Net-(Q2-C)") (class "Default")
      (node (ref "JP12") (pin "2") (pinfunction "2_2") (pintype "passive"))
      (node (ref "Q2") (pin "3") (pinfunction "C_3") (pintype "passive"))
    )
    (net (code "64") (name "Net-(Q3-B)") (class "Default")
      (node (ref "Q3") (pin "2") (pinfunction "B_2") (pintype "passive"))
      (node (ref "R15") (pin "2") (pinfunction "2_2") (pintype "passive"))
    )
    (net (code "65") (name "Net-(Q3-C)") (class "Default")
      (node (ref "JP13") (pin "2") (pinfunction "2_2") (pintype "passive"))
      (node (ref "Q3") (pin "3") (pinfunction "C_3") (pintype "passive"))
    )
    (net (code "66") (name "Net-(Q4-B)") (class "Default")
      (node (ref "Q4") (pin "2") (pinfunction "B_2") (pintype "passive"))
      (node (ref "R16") (pin "2") (pinfunction "2_2") (pintype "passive"))
    )
    (net (code "67") (name "Net-(Q4-C)") (class "Default")
      (node (ref "JP14") (pin "2") (pinfunction "2_2") (pintype "passive"))
      (node (ref "Q4") (pin "3") (pinfunction "C_3") (pintype "passive"))
    )
    (net (code "68") (name "Net-(Q5-B)") (class "Default")
      (node (ref "Q5") (pin "2") (pinfunction "B_2") (pintype "passive"))
      (node (ref "R21") (pin "2") (pinfunction "2_2") (pintype "passive"))
    )
    (net (code "69") (name "Net-(Q6-B)") (class "Default")
      (node (ref "Q6") (pin "2") (pinfunction "B_2") (pintype "passive"))
      (node (ref "R22") (pin "2") (pinfunction "2_2") (pintype "passive"))
    )
    (net (code "70") (name "Net-(Q7-B)") (class "Default")
      (node (ref "Q7") (pin "2") (pinfunction "B_2") (pintype "passive"))
      (node (ref "R23") (pin "2") (pinfunction "2_2") (pintype "passive"))
    )
    (net (code "71") (name "Net-(Q8-B)") (class "Default")
      (node (ref "Q8") (pin "2") (pinfunction "B_2") (pintype "passive"))
      (node (ref "R24") (pin "2") (pinfunction "2_2") (pintype "passive"))
    )
    (net (code "72") (name "Net-(Q9-PadG)") (class "Default")
      (node (ref "Q9") (pin "G") (pinfunction "G_G") (pintype "passive"))
      (node (ref "R25") (pin "2") (pinfunction "2_2") (pintype "passive"))
      (node (ref "R26") (pin "2") (pinfunction "2_2") (pintype "passive"))
    )
    (net (code "73") (name "Net-(R11-Pad1)") (class "Default")
      (node (ref "R11") (pin "1") (pinfunction "1_1") (pintype "passive"))
      (node (ref "R12") (pin "1") (pinfunction "1_1") (pintype "passive"))
      (node (ref "R17") (pin "E") (pinfunction "E_E") (pintype "passive"))
    )
    (net (code "74") (name "REVERSING") (class "Default")
      (node (ref "JP16") (pin "1") (pinfunction "1_1") (pintype "passive"))
      (node (ref "Q8") (pin "3") (pinfunction "C_3") (pintype "passive"))
    )
    (net (code "75") (name "TAILLIGHTS") (class "Default")
      (node (ref "JP16") (pin "3") (pinfunction "3_3") (pintype "passive"))
      (node (ref "Q7") (pin "3") (pinfunction "C_3") (pintype "passive"))
      (node (ref "R19") (pin "1") (pinfunction "1_1") (pintype "passive"))
    )
    (net (code "76") (name "unconnected-(IC2-L+-Pad7)") (class "Default")
      (node (ref "IC2") (pin "7") (pinfunction "L+_7") (pintype "output"))
    )
    (net (code "77") (name "unconnected-(IC2-L--Pad6)") (class "Default")
      (node (ref "IC2") (pin "6") (pinfunction "L-_6") (pintype "output"))
    )
    (net (code "78") (name "unconnected-(IC2-R+-Pad8)") (class "Default")
      (node (ref "IC2") (pin "8") (pinfunction "R+_8") (pintype "output"))
    )
    (net (code "79") (name "unconnected-(IC2-R--Pad9)") (class "Default")
      (node (ref "IC2") (pin "9") (pinfunction "R-_9") (pintype "output"))
    )
    (net (code "80") (name "unconnected-(JP16-Pad6)") (class "Default")
      (node (ref "JP16") (pin "6") (pinfunction "6_6") (pintype "passive"))
    )
    (net (code "81") (name "unconnected-(U1-IO0-PadD0)") (class "Default")
      (node (ref "U1") (pin "D0") (pinfunction "IO0_D0") (pintype "bidirectional"))
    )
    (net (code "82") (name "unconnected-(U1-IO6-PadD6)") (class "Default")
      (node (ref "U1") (pin "D6") (pinfunction "IO6_D6") (pintype "bidirectional"))
    )
    (net (code "83") (name "unconnected-(U1-IO7-PadD7)") (class "Default")
      (node (ref "U1") (pin "D7") (pinfunction "IO7_D7") (pintype "bidirectional"))
    )
    (net (code "84") (name "unconnected-(U1-IO8-PadD8)") (class "Default")
      (node (ref "U1") (pin "D8") (pinfunction "IO8_D8") (pintype "bidirectional"))
    )
    (net (code "85") (name "unconnected-(U1-IO9-PadD9)") (class "Default")
      (node (ref "U1") (pin "D9") (pinfunction "IO9_D9") (pintype "bidirectional"))
    )
    (net (code "86") (name "unconnected-(U1-IO10-PadD10)") (class "Default")
      (node (ref "U1") (pin "D10") (pinfunction "IO10_D10") (pintype "bidirectional"))
    )
    (net (code "87") (name "unconnected-(U1-IO11-PadD11)") (class "Default")
      (node (ref "U1") (pin "D11") (pinfunction "IO11_D11") (pintype "bidirectional"))
    )
    (net (code "88") (name "unconnected-(U1-Pad3V3)") (class "Default")
      (node (ref "U1") (pin "3V3") (pinfunction "3V3_3V3") (pintype "bidirectional"))
    )
    (net (code "89") (name "unconnected-(U1-PadEN)") (class "Default")
      (node (ref "U1") (pin "EN") (pinfunction "EN_EN") (pintype "bidirectional"))
    )
  )
)
